# Schematic.net
KiCad netlist of a schematic drawn in Altium Designer
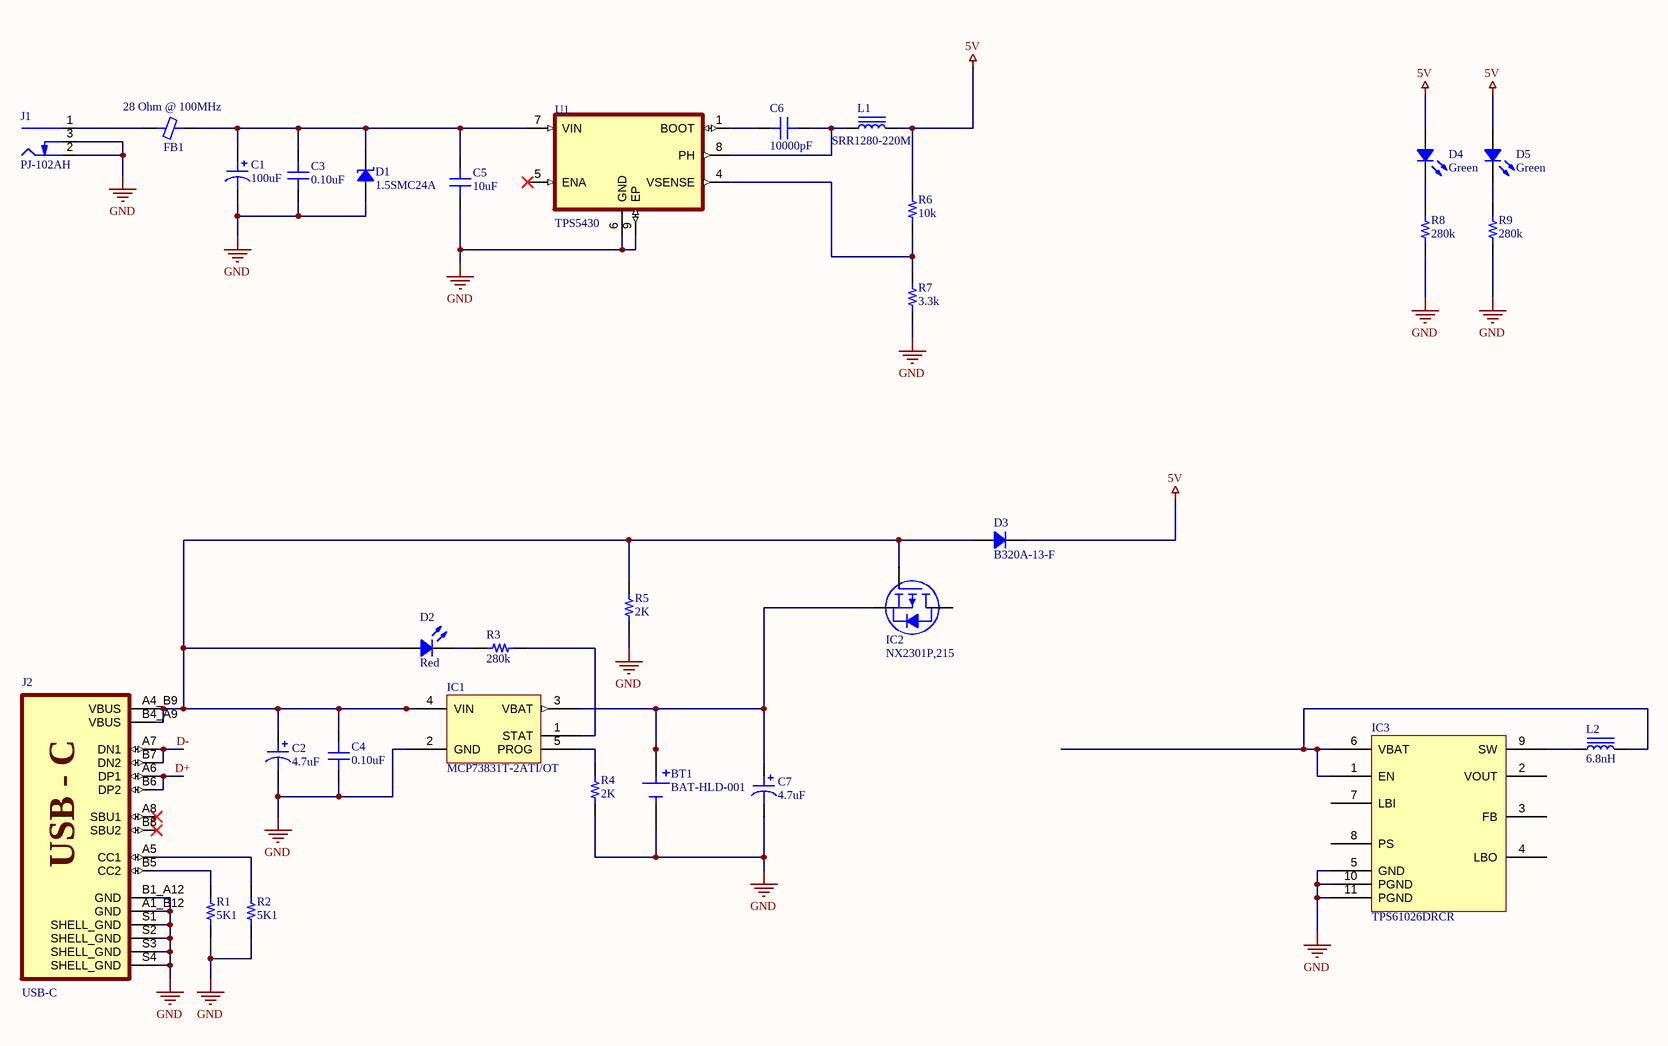
[diagram p0: Schematic.SchDoc]

(export (version "E")
  (design (tool "Eeschema 10.0.6"))
  (components
    (comp (ref "BT1")
      (value "BAT-HLD-001")
      (footprint "BAT_BAT-HLD-001")
      (description "Battery Retainer Coin, 20.0mm 1 Cell SMD (SMT) Tab")
      (libsource (lib "Own_Library") (part "BAT-HLD-001"))
    )
    (comp (ref "C1")
      (value "100uF")
      (footprint "CAP ALUM 10.3MM")
      (description "CAP ALUM 100UF 20% 50V SMD")
      (fields
        (field (name "PART NUMBER") "EEE-1HA101P")
        (field (name "MANUFACTURER") "Panasonic Electronic Components")
      )
      (libsource (lib "Capacitor - Aluminium") (part "EEE-1HA101P"))
    )
    (comp (ref "C2")
      (value "4.7uF")
      (footprint "CAP AL TH D10 L5 H14.5")
      (description "CAP ALUM 4.7UF 20% 160V RADIAL")
      (fields (field (name "PART NUMBER") "UPM2C4R7MPD1TD") (field (name "MANUFACTURER") "Nichicon"))
      (libsource (lib "Capacitor - Aluminium TH") (part "UPM2C4R7MPD1TD"))
    )
    (comp (ref "C3")
      (value "0.10uF")
      (footprint "CAP 0603/1608")
      (description "CAP CER 0.1UF 25V X7R 0603")
      (fields (field (name "PART NUMBER") "C0603C104J3RACTU") (field (name "MANUFACTURER") "Kemet"))
      (libsource (lib "Capacitor - Ceramic") (part "C0603C104J3RACTU"))
    )
    (comp (ref "C4")
      (value "0.10uF")
      (footprint "CAP 0603/1608")
      (description "CAP CER 0.1UF 25V X7R 0603")
      (fields (field (name "PART NUMBER") "C0603C104J3RACTU") (field (name "MANUFACTURER") "Kemet"))
      (libsource (lib "Capacitor - Ceramic") (part "C0603C104J3RACTU"))
    )
    (comp (ref "C5")
      (value "10uF")
      (footprint "CAP 1210/3225 - 2.8MM")
      (description "CAP CER 10UF 50V X7R 1210")
      (fields (field (name "PART NUMBER") "12105C106KAT2A") (field (name "MANUFACTURER") "AVX Corporation"))
      (libsource (lib "Capacitor - Ceramic") (part "12105C106KAT2A"))
    )
    (comp (ref "C6")
      (value "10000pF")
      (footprint "CAP 0805/2012")
      (description "CAP CER 10000PF 50V X7R 0805")
      (fields (field (name "PART NUMBER") "C0805C103K5RACAUTO") (field (name "MANUFACTURER") "Kemet"))
      (libsource (lib "Capacitor - Ceramic") (part "C0805C103K5RACAUTO"))
    )
    (comp (ref "C7")
      (value "4.7uF")
      (footprint "CAP AL TH D10 L5 H14.5")
      (description "CAP ALUM 4.7UF 20% 160V RADIAL")
      (fields (field (name "PART NUMBER") "UPM2C4R7MPD1TD") (field (name "MANUFACTURER") "Nichicon"))
      (libsource (lib "Capacitor - Aluminium TH") (part "UPM2C4R7MPD1TD"))
    )
    (comp (ref "D1")
      (value "1.5SMC24A")
      (footprint "DO214AB SMC")
      (description "TVS DIODE 20.5V 33.2V DO214AB")
      (fields (field (name "MANUFACTURER") "Littelfuse Inc."))
      (libsource (lib "Diodes - TVS") (part "1.5SMC24A"))
    )
    (comp (ref "D2")
      (value "Red")
      (footprint "LED 0603/1608 RED")
      (description "LED RED DIFFUSED 0603 SMD")
      (fields
        (field (name "PART NUMBER") "LS Q976-NR-1")
        (field (name "MANUFACTURER") "OSRAM Opto Semiconductors Inc.")
      )
      (libsource (lib "Chip LED") (part "LS Q976-NR-1"))
    )
    (comp (ref "D3")
      (value "B320A-13-F")
      (footprint "DO214AC SMA")
      (description "DIODE SCHOTTKY 20V 3A SMA")
      (fields (field (name "MANUFACTURER") "Diodes Incorporated"))
      (libsource (lib "Diode - Rectifier") (part "B320A-13-F"))
    )
    (comp (ref "D4")
      (value "Green")
      (footprint "LED 0603/1608 GREEN")
      (description "LED GREEN DIFFUSED 0603 SMD")
      (fields
        (field (name "PART NUMBER") "HSMQ-C191")
        (field (name "MANUFACTURER") "Avago Technologies US Inc.")
      )
      (libsource (lib "Chip LED") (part "HSMQ-C191"))
    )
    (comp (ref "D5")
      (value "Green")
      (footprint "LED 0603/1608 GREEN")
      (description "LED GREEN DIFFUSED 0603 SMD")
      (fields
        (field (name "PART NUMBER") "HSMQ-C191")
        (field (name "MANUFACTURER") "Avago Technologies US Inc.")
      )
      (libsource (lib "Chip LED") (part "HSMQ-C191"))
    )
    (comp (ref "FB1")
      (value "28 Ohm @ 100MHz")
      (footprint "FER 0603/1608")
      (description "FERRITE CHIP 28 OHM 4.0A 0603")
      (fields (field (name "PART NUMBER") "742792603") (field (name "MANUFACTURER") "Wurth Electronics Inc"))
      (libsource (lib "Ferrite Chip") (part "742792603"))
    )
    (comp (ref "IC1")
      (value "MCP73831T-2ATI/OT")
      (footprint "MICROCHIP SOT-23-5 OT")
      (description "IC CONTROLLR LI-ION 4.2V SOT23-5")
      (fields (field (name "MANUFACTURER") "Microchip Technology"))
      (libsource (lib "Charger") (part "MCP73831T-2ATI/OT"))
    )
    (comp (ref "IC2")
      (value "NX2301P,215")
      (footprint "NXP SOT-23-3 TO-236AB")
      (description "MOSFET P-CH 20V 2A TO-236AB")
      (fields (field (name "MANUFACTURER") "NXP Semiconductors"))
      (libsource (lib "P-Channel FET") (part "NX2301P,215"))
    )
    (comp (ref "IC3")
      (value "TPS61026DRCR")
      (footprint "TI PVSON-10 3x3MM DRC")
      (description "IC REG BOOST 5V 1.5A SYNC 10SON")
      (fields (field (name "MANUFACTURER") "Texas Instruments"))
      (libsource (lib "Voltage Regulator - Switchmode") (part "TPS61026DRCR"))
    )
    (comp (ref "J1")
      (value "PJ-102AH")
      (footprint "CUI PJ-102AH")
      (description "CONN PWR JACK 2X5.5MM SOLDER")
      (fields (field (name "MANUFACTURER") "CUI Devices"))
      (libsource (lib "Connectors - Barrel - Power") (part "PJ-102AH"))
    )
    (comp (ref "J2")
      (value "USB-C")
      (footprint "GCT_USB4105-GF-A")
      (fields (field (name "MP") "USB4105-GF-A"))
      (libsource (lib "Own_Library") (part "USB4105-GF-A"))
    )
    (comp (ref "L1")
      (value "SRR1280-220M")
      (footprint "BOURNS SRR1280")
      (description "FIXED IND 22UH 4.3A 38.6 MOHM")
      (fields (field (name "MANUFACTURER") "Bourns Inc.") (field (name "TOLERANCE") "20%"))
      (libsource (lib "Inductor - Power") (part "SRR1280-220M"))
    )
    (comp (ref "L2")
      (value "6.8nH")
      (footprint "IND 0402/1005 RF WW")
      (description "FIXED IND 6.8NH 700MA 90 MOHM")
      (fields
        (field (name "PART NUMBER") "LQW15AN6N8G00D")
        (field (name "MANUFACTURER") "Murata Electronics North America")
      )
      (libsource (lib "Inductor - RF") (part "LQW15AN6N8G00D"))
    )
    (comp (ref "R1")
      (value "5K1")
      (footprint "RES 0603/1608")
      (description "RES SMD 5K1 OHM 5% 1/8W 0603")
      (fields (field (name "PART NUMBER") "0603S8J0512") (field (name "MANUFACTURER") "Uniohm"))
      (libsource (lib "Resistor - Chip - Uniohm") (part "0603S8J0512"))
    )
    (comp (ref "R2")
      (value "5K1")
      (footprint "RES 0603/1608")
      (description "RES SMD 5K1 OHM 5% 1/8W 0603")
      (fields (field (name "PART NUMBER") "0603S8J0512") (field (name "MANUFACTURER") "Uniohm"))
      (libsource (lib "Resistor - Chip - Uniohm") (part "0603S8J0512"))
    )
    (comp (ref "R3")
      (value "280k")
      (footprint "RES 1206/3216")
      (description "RES SMD 280K OHM 0.1% 1/4W 1206")
      (fields
        (field (name "PART NUMBER") "ERA-8AEB2803V")
        (field (name "MANUFACTURER") "Panasonic Electronic Components")
      )
      (libsource (lib "Resistor - Chip") (part "ERA-8AEB2803V"))
    )
    (comp (ref "R4")
      (value "2K")
      (footprint "RES 0603/1608")
      (description "RES SMD 2K OHM 5% 1/8W 0603")
      (fields (field (name "PART NUMBER") "0603S8J0202") (field (name "MANUFACTURER") "Uniohm"))
      (libsource (lib "Resistor - Chip - Uniohm") (part "0603S8J0202"))
    )
    (comp (ref "R5")
      (value "2K")
      (footprint "RES 0805/2012")
      (description "RES SMD 2K OHM 5% 1/8W 0805")
      (fields (field (name "PART NUMBER") "0805S8J0202") (field (name "MANUFACTURER") "Uniohm"))
      (libsource (lib "Resistor - Chip - Uniohm") (part "0805S8J0202"))
    )
    (comp (ref "R6")
      (value "10k")
      (footprint "RES 0603/1608")
      (description "RES SMD 10K OHM 0.1% 1/10W 0603")
      (fields
        (field (name "PART NUMBER") "ERA-3AEB103V")
        (field (name "MANUFACTURER") "Panasonic Electronic Components")
      )
      (libsource (lib "Resistor - Chip") (part "ERA-3AEB103V"))
    )
    (comp (ref "R7")
      (value "3.3k")
      (footprint "RES 0603/1608")
      (description "RES SMD 3.3K OHM 0.1% 1/10W 0603")
      (fields
        (field (name "PART NUMBER") "ERA-3APB332V")
        (field (name "MANUFACTURER") "Panasonic Electronic Components")
      )
      (libsource (lib "Resistor - Chip") (part "ERA-3APB332V"))
    )
    (comp (ref "R8")
      (value "280k")
      (footprint "RES 1206/3216")
      (description "RES SMD 280K OHM 0.1% 1/4W 1206")
      (fields
        (field (name "PART NUMBER") "ERA-8AEB2803V")
        (field (name "MANUFACTURER") "Panasonic Electronic Components")
      )
      (libsource (lib "Resistor - Chip") (part "ERA-8AEB2803V"))
    )
    (comp (ref "R9")
      (value "280k")
      (footprint "RES 1206/3216")
      (description "RES SMD 280K OHM 0.1% 1/4W 1206")
      (fields
        (field (name "PART NUMBER") "ERA-8AEB2803V")
        (field (name "MANUFACTURER") "Panasonic Electronic Components")
      )
      (libsource (lib "Resistor - Chip") (part "ERA-8AEB2803V"))
    )
    (comp (ref "U1")
      (value "TPS5430")
      (footprint "VREG_LM5017MR/NOPB")
      (description "CONVERTER 5.5V-36 to 5.5V")
      (fields (field (name "MF") "Texas Instruments") (field (name "MP") "TPS5430DDA"))
      (libsource (lib "Own_Library") (part "TPS5430DDA"))
    )
  )
  (nets
    (net (code "1") (name "/D+") (class "Default")
      (node (ref "J2") (pin "A6") (pinfunction "DP1_A6") (pintype "bidirectional"))
      (node (ref "J2") (pin "B6") (pinfunction "DP2_B6") (pintype "bidirectional"))
    )
    (net (code "2") (name "/D-") (class "Default")
      (node (ref "J2") (pin "A7") (pinfunction "DN1_A7") (pintype "bidirectional"))
      (node (ref "J2") (pin "B7") (pinfunction "DN2_B7") (pintype "bidirectional"))
    )
    (net (code "3") (name "5V") (class "Default")
      (node (ref "D3") (pin "2") (pinfunction "2_2") (pintype "passive"))
      (node (ref "D4") (pin "1") (pinfunction "1_1") (pintype "passive"))
      (node (ref "D5") (pin "1") (pinfunction "1_1") (pintype "passive"))
      (node (ref "L1") (pin "2") (pinfunction "2_2") (pintype "passive"))
      (node (ref "R6") (pin "2") (pinfunction "2_2") (pintype "passive"))
    )
    (net (code "4") (name "GND") (class "Default")
      (node (ref "BT1") (pin "N1") (pinfunction "NEG_N1") (pintype "passive"))
      (node (ref "C1") (pin "2") (pinfunction "2_2") (pintype "passive"))
      (node (ref "C2") (pin "2") (pinfunction "2_2") (pintype "passive"))
      (node (ref "C3") (pin "1") (pinfunction "1_1") (pintype "passive"))
      (node (ref "C4") (pin "1") (pinfunction "1_1") (pintype "passive"))
      (node (ref "C5") (pin "2") (pinfunction "2_2") (pintype "passive"))
      (node (ref "C7") (pin "2") (pinfunction "2_2") (pintype "passive"))
      (node (ref "D1") (pin "1") (pinfunction "1_1") (pintype "passive"))
      (node (ref "IC1") (pin "2") (pinfunction "GND_2") (pintype "passive"))
      (node (ref "IC3") (pin "10") (pinfunction "PGND_10") (pintype "passive"))
      (node (ref "IC3") (pin "11") (pinfunction "PGND_11") (pintype "passive"))
      (node (ref "IC3") (pin "5") (pinfunction "GND_5") (pintype "passive"))
      (node (ref "J1") (pin "2") (pinfunction "Outer_2") (pintype "passive"))
      (node (ref "J1") (pin "3") (pinfunction "SW_3") (pintype "passive"))
      (node (ref "J2") (pin "A1_B12") (pinfunction "GND_A1_B12") (pintype "power_in"))
      (node (ref "J2") (pin "B1_A12") (pinfunction "GND_B1_A12") (pintype "power_in"))
      (node (ref "J2") (pin "S1") (pinfunction "SHELL_GND_S1") (pintype "power_in"))
      (node (ref "J2") (pin "S2") (pinfunction "SHELL_GND_S2") (pintype "power_in"))
      (node (ref "J2") (pin "S3") (pinfunction "SHELL_GND_S3") (pintype "power_in"))
      (node (ref "J2") (pin "S4") (pinfunction "SHELL_GND_S4") (pintype "power_in"))
      (node (ref "R1") (pin "1") (pinfunction "1_1") (pintype "passive"))
      (node (ref "R2") (pin "1") (pinfunction "1_1") (pintype "passive"))
      (node (ref "R4") (pin "1") (pinfunction "1_1") (pintype "passive"))
      (node (ref "R5") (pin "1") (pinfunction "1_1") (pintype "passive"))
      (node (ref "R7") (pin "1") (pinfunction "1_1") (pintype "passive"))
      (node (ref "R8") (pin "2") (pinfunction "2_2") (pintype "passive"))
      (node (ref "R9") (pin "2") (pinfunction "2_2") (pintype "passive"))
      (node (ref "U1") (pin "6") (pinfunction "GND_6") (pintype "power_in"))
      (node (ref "U1") (pin "9") (pinfunction "EP_9") (pintype "bidirectional"))
    )
    (net (code "5") (name "Net-(D2-Pad2)") (class "Default")
      (node (ref "D2") (pin "2") (pinfunction "2_2") (pintype "passive"))
      (node (ref "R3") (pin "1") (pinfunction "1_1") (pintype "passive"))
    )
    (net (code "6") (name "Net-(D4-Pad2)") (class "Default")
      (node (ref "D4") (pin "2") (pinfunction "2_2") (pintype "passive"))
      (node (ref "R8") (pin "1") (pinfunction "1_1") (pintype "passive"))
    )
    (net (code "7") (name "Net-(D5-Pad2)") (class "Default")
      (node (ref "D5") (pin "2") (pinfunction "2_2") (pintype "passive"))
      (node (ref "R9") (pin "1") (pinfunction "1_1") (pintype "passive"))
    )
    (net (code "8") (name "Net-(IC1-PROG)") (class "Default")
      (node (ref "IC1") (pin "5") (pinfunction "PROG_5") (pintype "passive"))
      (node (ref "R4") (pin "2") (pinfunction "2_2") (pintype "passive"))
    )
    (net (code "9") (name "Net-(IC1-STAT)") (class "Default")
      (node (ref "IC1") (pin "1") (pinfunction "STAT_1") (pintype "passive"))
      (node (ref "R3") (pin "2") (pinfunction "2_2") (pintype "passive"))
    )
    (net (code "10") (name "Net-(IC1-VBAT)") (class "Default")
      (node (ref "BT1") (pin "P1") (pinfunction "POS_P1") (pintype "passive"))
      (node (ref "BT1") (pin "P2") (pinfunction "POS_P2") (pintype "passive"))
      (node (ref "C7") (pin "1") (pinfunction "1_1") (pintype "passive"))
      (node (ref "IC1") (pin "3") (pinfunction "VBAT_3") (pintype "output"))
      (node (ref "IC2") (pin "3") (pinfunction "S_3") (pintype "passive"))
    )
    (net (code "11") (name "Net-(IC1-VIN)") (class "Default")
      (node (ref "C2") (pin "1") (pinfunction "1_1") (pintype "passive"))
      (node (ref "C4") (pin "2") (pinfunction "2_2") (pintype "passive"))
      (node (ref "D2") (pin "1") (pinfunction "1_1") (pintype "passive"))
      (node (ref "D3") (pin "1") (pinfunction "1_1") (pintype "passive"))
      (node (ref "IC1") (pin "4") (pinfunction "VIN_4") (pintype "passive"))
      (node (ref "IC2") (pin "1") (pinfunction "G_1") (pintype "passive"))
      (node (ref "J2") (pin "A4_B9") (pinfunction "VBUS_A4_B9") (pintype "power_in"))
      (node (ref "J2") (pin "B4_A9") (pinfunction "VBUS_B4_A9") (pintype "power_in"))
      (node (ref "R5") (pin "2") (pinfunction "2_2") (pintype "passive"))
    )
    (net (code "12") (name "Net-(IC3-EN)") (class "Default")
      (node (ref "IC3") (pin "1") (pinfunction "EN_1") (pintype "passive"))
      (node (ref "IC3") (pin "6") (pinfunction "VBAT_6") (pintype "passive"))
      (node (ref "L2") (pin "2") (pinfunction "2_2") (pintype "passive"))
    )
    (net (code "13") (name "Net-(IC3-SW)") (class "Default")
      (node (ref "IC3") (pin "9") (pinfunction "SW_9") (pintype "passive"))
      (node (ref "L2") (pin "1") (pinfunction "1_1") (pintype "passive"))
    )
    (net (code "14") (name "Net-(J1-Centre)") (class "Default")
      (node (ref "FB1") (pin "1") (pinfunction "1_1") (pintype "passive"))
      (node (ref "J1") (pin "1") (pinfunction "Centre_1") (pintype "passive"))
    )
    (net (code "15") (name "Net-(J2-CC1)") (class "Default")
      (node (ref "J2") (pin "A5") (pinfunction "CC1_A5") (pintype "bidirectional"))
      (node (ref "R2") (pin "2") (pinfunction "2_2") (pintype "passive"))
    )
    (net (code "16") (name "Net-(J2-CC2)") (class "Default")
      (node (ref "J2") (pin "B5") (pinfunction "CC2_B5") (pintype "bidirectional"))
      (node (ref "R1") (pin "2") (pinfunction "2_2") (pintype "passive"))
    )
    (net (code "17") (name "Net-(U1-BOOT)") (class "Default")
      (node (ref "C6") (pin "1") (pinfunction "1_1") (pintype "passive"))
      (node (ref "U1") (pin "1") (pinfunction "BOOT_1") (pintype "bidirectional"))
    )
    (net (code "18") (name "Net-(U1-PH)") (class "Default")
      (node (ref "C6") (pin "2") (pinfunction "2_2") (pintype "passive"))
      (node (ref "L1") (pin "1") (pinfunction "1_1") (pintype "passive"))
      (node (ref "U1") (pin "8") (pinfunction "PH_8") (pintype "output"))
    )
    (net (code "19") (name "Net-(U1-VIN)") (class "Default")
      (node (ref "C1") (pin "1") (pinfunction "1_1") (pintype "passive"))
      (node (ref "C3") (pin "2") (pinfunction "2_2") (pintype "passive"))
      (node (ref "C5") (pin "1") (pinfunction "1_1") (pintype "passive"))
      (node (ref "D1") (pin "2") (pinfunction "2_2") (pintype "passive"))
      (node (ref "FB1") (pin "2") (pinfunction "2_2") (pintype "passive"))
      (node (ref "U1") (pin "7") (pinfunction "VIN_7") (pintype "input"))
    )
    (net (code "20") (name "Net-(U1-VSENSE)") (class "Default")
      (node (ref "R6") (pin "1") (pinfunction "1_1") (pintype "passive"))
      (node (ref "R7") (pin "2") (pinfunction "2_2") (pintype "passive"))
      (node (ref "U1") (pin "4") (pinfunction "VSENSE_4") (pintype "output"))
    )
    (net (code "21") (name "unconnected-(IC2-D-Pad2)") (class "Default")
      (node (ref "IC2") (pin "2") (pinfunction "D_2") (pintype "passive"))
    )
    (net (code "22") (name "unconnected-(IC3-FB-Pad3)") (class "Default")
      (node (ref "IC3") (pin "3") (pinfunction "FB_3") (pintype "passive"))
    )
    (net (code "23") (name "unconnected-(IC3-LBI-Pad7)") (class "Default")
      (node (ref "IC3") (pin "7") (pinfunction "LBI_7") (pintype "passive"))
    )
    (net (code "24") (name "unconnected-(IC3-LBO-Pad4)") (class "Default")
      (node (ref "IC3") (pin "4") (pinfunction "LBO_4") (pintype "passive"))
    )
    (net (code "25") (name "unconnected-(IC3-PS-Pad8)") (class "Default")
      (node (ref "IC3") (pin "8") (pinfunction "PS_8") (pintype "passive"))
    )
    (net (code "26") (name "unconnected-(IC3-VOUT-Pad2)") (class "Default")
      (node (ref "IC3") (pin "2") (pinfunction "VOUT_2") (pintype "passive"))
    )
    (net (code "27") (name "unconnected-(J2-SBU1-PadA8)") (class "Default")
      (node (ref "J2") (pin "A8") (pinfunction "SBU1_A8") (pintype "bidirectional+no_connect"))
    )
    (net (code "28") (name "unconnected-(J2-SBU2-PadB8)") (class "Default")
      (node (ref "J2") (pin "B8") (pinfunction "SBU2_B8") (pintype "bidirectional+no_connect"))
    )
    (net (code "29") (name "unconnected-(U1-ENA-Pad5)") (class "Default")
      (node (ref "U1") (pin "5") (pinfunction "ENA_5") (pintype "input+no_connect"))
    )
  )
)
